# untitled8266.net
KiCad netlist of a schematic drawn in EAGLE
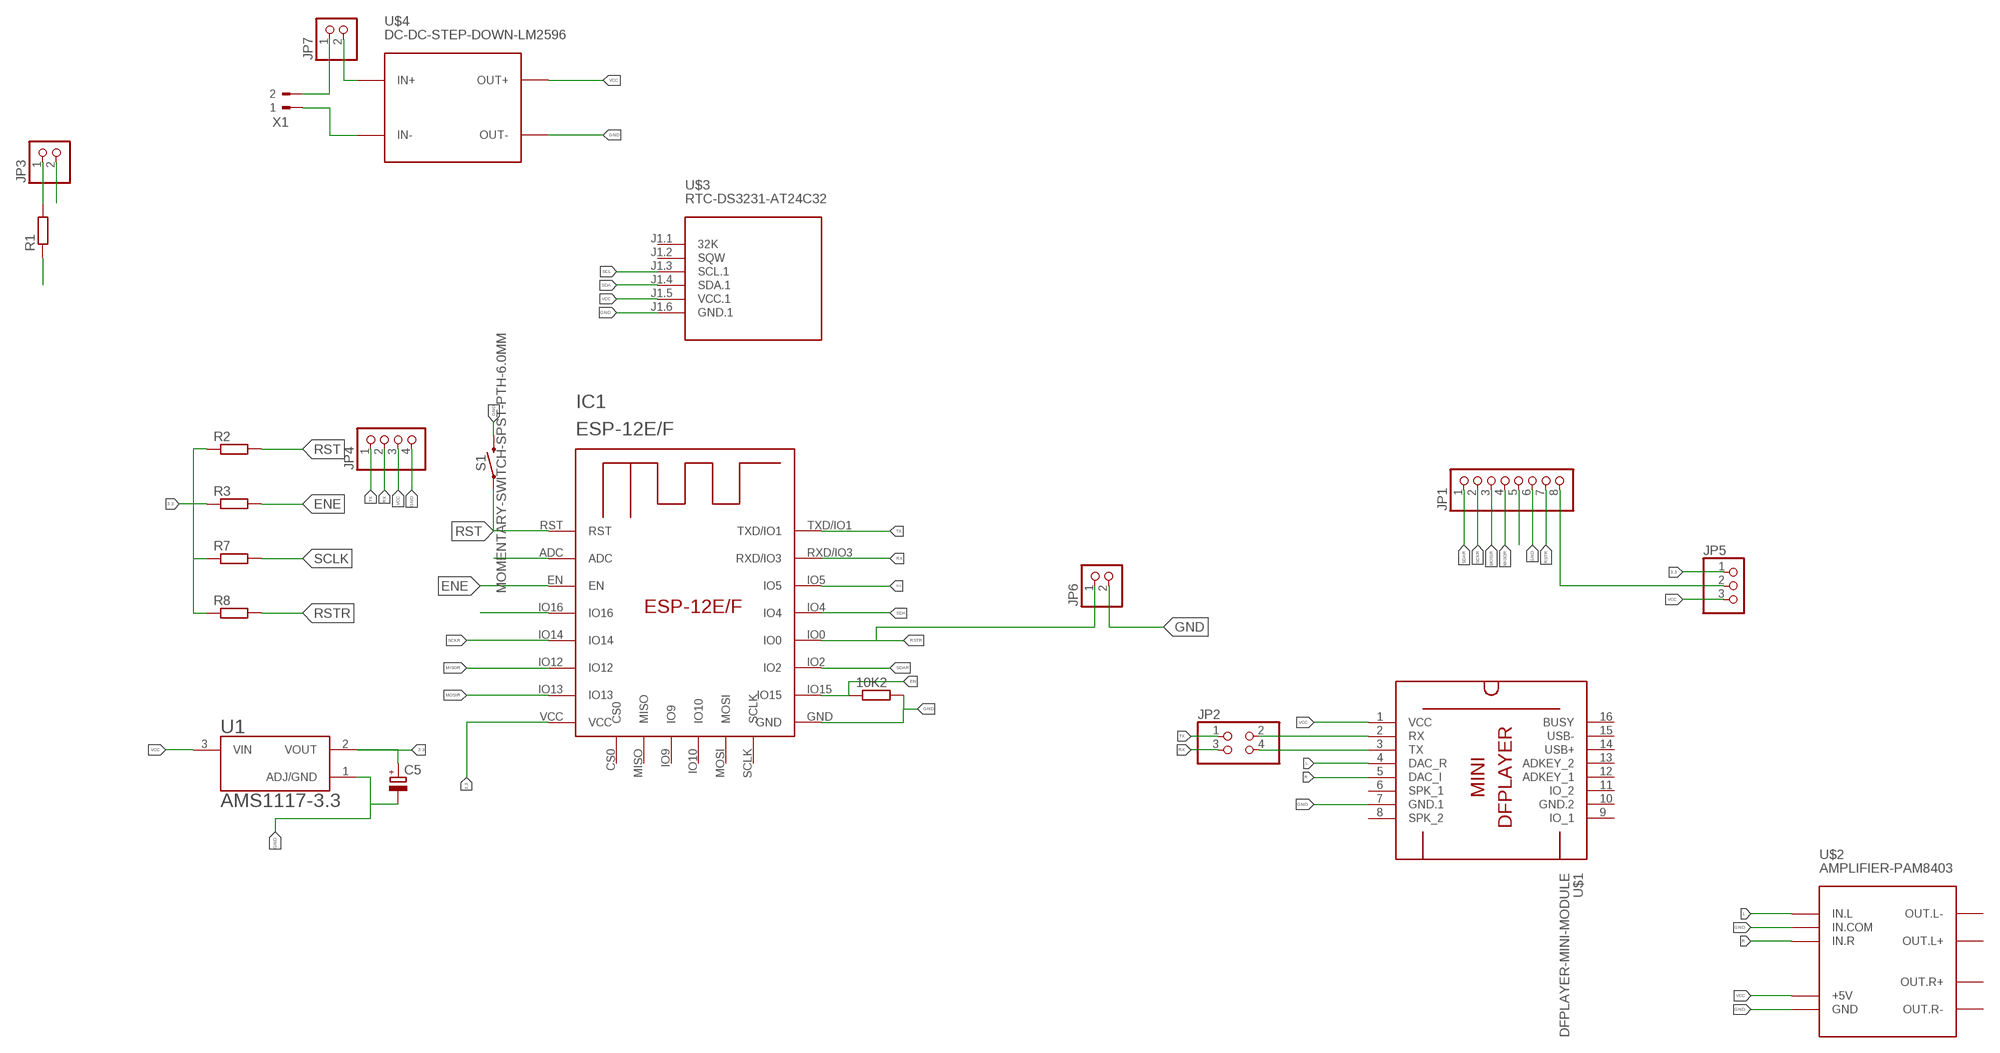
[diagram p0: schematic, sheet 1]

(export (version "E")
  (design (tool "Eeschema 10.0.6"))
  (components
    (comp (ref "10K2")
      (value "R-EU_0207/10")
      (footprint "eagle-import:0207_10")
      (libsource (lib "eagle-import") (part "R-EU_0207/10"))
    )
    (comp (ref "C5")
      (value "CPOL-EUE5-10.5")
      (footprint "eagle-import:E5-10,5")
      (libsource (lib "eagle-import") (part "CPOL-EUE5-10.5"))
    )
    (comp (ref "IC1")
      (value "ESP-12E/F")
      (footprint "eagle-import:ESP-12E")
      (libsource (lib "eagle-import") (part "ESP-12E/F"))
    )
    (comp (ref "JP1")
      (value "PINHD-1X8")
      (footprint "eagle-import:1X08")
      (libsource (lib "eagle-import") (part "PINHD-1X8"))
    )
    (comp (ref "JP2")
      (value "PINHD-2X2")
      (footprint "eagle-import:2X02")
      (libsource (lib "eagle-import") (part "PINHD-2X2"))
    )
    (comp (ref "JP3")
      (value "PINHD-1X2")
      (footprint "eagle-import:1X02")
      (libsource (lib "eagle-import") (part "PINHD-1X2"))
    )
    (comp (ref "JP4")
      (value "PINHD-1X4")
      (footprint "eagle-import:1X04")
      (libsource (lib "eagle-import") (part "PINHD-1X4"))
    )
    (comp (ref "JP5")
      (value "PINHD-1X3")
      (footprint "eagle-import:1X03")
      (libsource (lib "eagle-import") (part "PINHD-1X3"))
    )
    (comp (ref "JP6")
      (value "PINHD-1X2")
      (footprint "eagle-import:1X02")
      (libsource (lib "eagle-import") (part "PINHD-1X2"))
    )
    (comp (ref "JP7")
      (value "PINHD-1X2")
      (footprint "eagle-import:1X02")
      (libsource (lib "eagle-import") (part "PINHD-1X2"))
    )
    (comp (ref "R1")
      (value "R-EU_0207/10")
      (footprint "eagle-import:0207_10")
      (libsource (lib "eagle-import") (part "R-EU_0207/10"))
    )
    (comp (ref "R2")
      (value "R-EU_0207/10")
      (footprint "eagle-import:0207_10")
      (libsource (lib "eagle-import") (part "R-EU_0207/10"))
    )
    (comp (ref "R3")
      (value "R-EU_0207/10")
      (footprint "eagle-import:0207_10")
      (libsource (lib "eagle-import") (part "R-EU_0207/10"))
    )
    (comp (ref "R7")
      (value "R-EU_0207/10")
      (footprint "eagle-import:0207_10")
      (libsource (lib "eagle-import") (part "R-EU_0207/10"))
    )
    (comp (ref "R8")
      (value "R-EU_0207/10")
      (footprint "eagle-import:0207_10")
      (libsource (lib "eagle-import") (part "R-EU_0207/10"))
    )
    (comp (ref "S1")
      (value "MOMENTARY-SWITCH-SPST-PTH-6.0MM")
      (footprint "eagle-import:TACTILE_SWITCH_PTH_6.0MM")
      (libsource (lib "eagle-import") (part "MOMENTARY-SWITCH-SPST-PTH-6.0MM"))
    )
    (comp (ref "U$1")
      (value "DFPLAYER-MINI-MODULE")
      (footprint "eagle-import:DFPLAYER-MINI-MODULE")
      (libsource (lib "eagle-import") (part "DFPLAYER-MINI-MODULE"))
    )
    (comp (ref "U$2")
      (value "AMPLIFIER-PAM8403")
      (footprint "eagle-import:AMPLIFIER-PAM8403")
      (libsource (lib "eagle-import") (part "AMPLIFIER-PAM8403"))
    )
    (comp (ref "U$3")
      (value "RTC-DS3231-AT24C32")
      (footprint "eagle-import:RTC-DS3231-AT24C32")
      (libsource (lib "eagle-import") (part "RTC-DS3231-AT24C32"))
    )
    (comp (ref "U$4")
      (value "DC-DC-STEP-DOWN-LM2596")
      (footprint "eagle-import:DC-DC-STEP-DOWN-LM2596")
      (libsource (lib "eagle-import") (part "DC-DC-STEP-DOWN-LM2596"))
    )
    (comp (ref "U1")
      (value "AMS1117-3.3")
      (footprint "eagle-import:SOT229P700X180-4N")
      (fields (field (name "MF") "Advanced Monolithic Systems"))
      (libsource (lib "eagle-import") (part "AMS1117-3.3"))
    )
    (comp (ref "X1")
      (value "180-2")
      (footprint "eagle-import:180-2")
      (libsource (lib "eagle-import") (part "180-2"))
    )
  )
  (nets
    (net (code "1") (name "/GND.2") (class "Default")
      (node (ref "U$1") (pin "10") (pinfunction "GND.2_10") (pintype "power_in"))
    )
    (net (code "2") (name "3.3") (class "Default")
      (node (ref "C5") (pin "+") (pinfunction "+_+") (pintype "passive"))
      (node (ref "IC1") (pin "VCC") (pinfunction "VCC_VCC") (pintype "power_in"))
      (node (ref "JP5") (pin "1") (pinfunction "1_1") (pintype "passive"))
      (node (ref "R2") (pin "1") (pinfunction "1_1") (pintype "passive"))
      (node (ref "R3") (pin "1") (pinfunction "1_1") (pintype "passive"))
      (node (ref "R7") (pin "1") (pinfunction "1_1") (pintype "passive"))
      (node (ref "R8") (pin "1") (pinfunction "1_1") (pintype "passive"))
      (node (ref "U1") (pin "2") (pinfunction "VOUT_2") (pintype "output"))
    )
    (net (code "3") (name "EN") (class "Default")
      (node (ref "10K2") (pin "1") (pinfunction "1_1") (pintype "passive"))
      (node (ref "IC1") (pin "IO15") (pinfunction "IO15_IO15") (pintype "bidirectional"))
    )
    (net (code "4") (name "ENE") (class "Default")
      (node (ref "IC1") (pin "EN") (pinfunction "EN_EN") (pintype "bidirectional"))
      (node (ref "R3") (pin "2") (pinfunction "2_2") (pintype "passive"))
    )
    (net (code "5") (name "GND") (class "Default")
      (node (ref "10K2") (pin "2") (pinfunction "2_2") (pintype "passive"))
      (node (ref "C5") (pin "-") (pinfunction "-_-") (pintype "passive"))
      (node (ref "IC1") (pin "GND") (pinfunction "GND_GND") (pintype "power_in"))
      (node (ref "JP1") (pin "6") (pinfunction "6_6") (pintype "passive"))
      (node (ref "JP3") (pin "2") (pinfunction "2_2") (pintype "passive"))
      (node (ref "JP4") (pin "4") (pinfunction "4_4") (pintype "passive"))
      (node (ref "JP6") (pin "2") (pinfunction "2_2") (pintype "passive"))
      (node (ref "S1") (pin "3") (pinfunction "2_3") (pintype "passive"))
      (node (ref "U$1") (pin "7") (pinfunction "GND.1_7") (pintype "power_in"))
      (node (ref "U$2") (pin "GND") (pinfunction "GND_GND") (pintype "power_in"))
      (node (ref "U$2") (pin "IN.COM") (pinfunction "IN.COM_IN.COM") (pintype "input"))
      (node (ref "U$3") (pin "J1.6") (pinfunction "GND.1_J1.6") (pintype "power_in"))
      (node (ref "U$4") (pin "OUT-") (pinfunction "OUT-_OUT-") (pintype "bidirectional"))
      (node (ref "U1") (pin "1") (pinfunction "ADJ/GND_1") (pintype "power_in"))
    )
    (net (code "6") (name "L") (class "Default")
      (node (ref "U$1") (pin "4") (pinfunction "DAC_R_4") (pintype "bidirectional"))
      (node (ref "U$2") (pin "IN.L") (pinfunction "IN.L_IN.L") (pintype "input"))
    )
    (net (code "7") (name "MISOR") (class "Default")
      (node (ref "IC1") (pin "IO12") (pinfunction "IO12_IO12") (pintype "bidirectional"))
      (node (ref "JP1") (pin "4") (pinfunction "4_4") (pintype "passive"))
    )
    (net (code "8") (name "MOSIR") (class "Default")
      (node (ref "IC1") (pin "IO13") (pinfunction "IO13_IO13") (pintype "bidirectional"))
      (node (ref "JP1") (pin "3") (pinfunction "3_3") (pintype "passive"))
    )
    (net (code "9") (name "Net-(JP1-Pad8)") (class "Default")
      (node (ref "JP1") (pin "8") (pinfunction "8_8") (pintype "passive"))
      (node (ref "JP5") (pin "2") (pinfunction "2_2") (pintype "passive"))
    )
    (net (code "10") (name "Net-(JP3-Pad1)") (class "Default")
      (node (ref "JP3") (pin "1") (pinfunction "1_1") (pintype "passive"))
      (node (ref "R1") (pin "2") (pinfunction "2_2") (pintype "passive"))
    )
    (net (code "11") (name "Net-(JP7-Pad1)") (class "Default")
      (node (ref "JP7") (pin "1") (pinfunction "1_1") (pintype "passive"))
      (node (ref "X1") (pin "2") (pinfunction "2_2") (pintype "passive"))
    )
    (net (code "12") (name "Net-(JP7-Pad2)") (class "Default")
      (node (ref "JP7") (pin "2") (pinfunction "2_2") (pintype "passive"))
      (node (ref "U$4") (pin "IN+") (pinfunction "IN+_IN+") (pintype "bidirectional"))
    )
    (net (code "13") (name "Net-(U$1-RX)") (class "Default")
      (node (ref "JP2") (pin "2") (pinfunction "2_2") (pintype "passive"))
      (node (ref "U$1") (pin "2") (pinfunction "RX_2") (pintype "bidirectional"))
    )
    (net (code "14") (name "Net-(U$1-TX)") (class "Default")
      (node (ref "JP2") (pin "4") (pinfunction "4_4") (pintype "passive"))
      (node (ref "U$1") (pin "3") (pinfunction "TX_3") (pintype "bidirectional"))
    )
    (net (code "15") (name "Net-(U$4-PadIN-)") (class "Default")
      (node (ref "U$4") (pin "IN-") (pinfunction "IN-_IN-") (pintype "bidirectional"))
      (node (ref "X1") (pin "1") (pinfunction "1_1") (pintype "passive"))
    )
    (net (code "16") (name "R") (class "Default")
      (node (ref "U$1") (pin "5") (pinfunction "DAC_I_5") (pintype "bidirectional"))
      (node (ref "U$2") (pin "IN.R") (pinfunction "IN.R_IN.R") (pintype "bidirectional"))
    )
    (net (code "17") (name "RST") (class "Default")
      (node (ref "IC1") (pin "RST") (pinfunction "RST_RST") (pintype "input"))
      (node (ref "R2") (pin "2") (pinfunction "2_2") (pintype "passive"))
      (node (ref "S1") (pin "1") (pinfunction "1_1") (pintype "passive"))
    )
    (net (code "18") (name "RSTR") (class "Default")
      (node (ref "IC1") (pin "IO0") (pinfunction "IO0_IO0") (pintype "bidirectional"))
      (node (ref "JP1") (pin "7") (pinfunction "7_7") (pintype "passive"))
      (node (ref "JP6") (pin "1") (pinfunction "1_1") (pintype "passive"))
      (node (ref "R8") (pin "2") (pinfunction "2_2") (pintype "passive"))
    )
    (net (code "19") (name "RX") (class "Default")
      (node (ref "IC1") (pin "RXD/IO3") (pinfunction "RXD/IO3_RXD/IO3") (pintype "bidirectional"))
      (node (ref "JP2") (pin "3") (pinfunction "3_3") (pintype "passive"))
      (node (ref "JP4") (pin "2") (pinfunction "2_2") (pintype "passive"))
    )
    (net (code "20") (name "SCKR") (class "Default")
      (node (ref "IC1") (pin "IO14") (pinfunction "IO14_IO14") (pintype "bidirectional"))
      (node (ref "JP1") (pin "2") (pinfunction "2_2") (pintype "passive"))
    )
    (net (code "21") (name "SCL") (class "Default")
      (node (ref "IC1") (pin "IO5") (pinfunction "IO5_IO5") (pintype "bidirectional"))
      (node (ref "U$3") (pin "J1.3") (pinfunction "SCL.1_J1.3") (pintype "bidirectional"))
    )
    (net (code "22") (name "SCLK") (class "Default")
      (node (ref "R7") (pin "2") (pinfunction "2_2") (pintype "passive"))
    )
    (net (code "23") (name "SDA") (class "Default")
      (node (ref "IC1") (pin "IO4") (pinfunction "IO4_IO4") (pintype "bidirectional"))
      (node (ref "U$3") (pin "J1.4") (pinfunction "SDA.1_J1.4") (pintype "bidirectional"))
    )
    (net (code "24") (name "SDAR") (class "Default")
      (node (ref "IC1") (pin "IO2") (pinfunction "IO2_IO2") (pintype "bidirectional"))
      (node (ref "JP1") (pin "1") (pinfunction "1_1") (pintype "passive"))
    )
    (net (code "25") (name "TX") (class "Default")
      (node (ref "IC1") (pin "TXD/IO1") (pinfunction "TXD/IO1_TXD/IO1") (pintype "bidirectional"))
      (node (ref "JP2") (pin "1") (pinfunction "1_1") (pintype "passive"))
      (node (ref "JP4") (pin "1") (pinfunction "1_1") (pintype "passive"))
    )
    (net (code "26") (name "VCC") (class "Default")
      (node (ref "JP4") (pin "3") (pinfunction "3_3") (pintype "passive"))
      (node (ref "JP5") (pin "3") (pinfunction "3_3") (pintype "passive"))
      (node (ref "R1") (pin "1") (pinfunction "1_1") (pintype "passive"))
      (node (ref "U$1") (pin "1") (pinfunction "VCC_1") (pintype "power_in"))
      (node (ref "U$2") (pin "+5V") (pinfunction "+5V_+5V") (pintype "power_in"))
      (node (ref "U$3") (pin "J1.5") (pinfunction "VCC.1_J1.5") (pintype "power_in"))
      (node (ref "U$4") (pin "OUT+") (pinfunction "OUT+_OUT+") (pintype "bidirectional"))
      (node (ref "U1") (pin "3") (pinfunction "VIN_3") (pintype "input"))
    )
    (net (code "27") (name "unconnected-(IC1-PadADC)") (class "Default")
      (node (ref "IC1") (pin "ADC") (pinfunction "ADC_ADC") (pintype "bidirectional"))
    )
    (net (code "28") (name "unconnected-(IC1-PadCS0)") (class "Default")
      (node (ref "IC1") (pin "CS0") (pinfunction "CS0_CS0") (pintype "bidirectional"))
    )
    (net (code "29") (name "unconnected-(IC1-PadIO9)") (class "Default")
      (node (ref "IC1") (pin "IO9") (pinfunction "IO9_IO9") (pintype "bidirectional"))
    )
    (net (code "30") (name "unconnected-(IC1-PadIO10)") (class "Default")
      (node (ref "IC1") (pin "IO10") (pinfunction "IO10_IO10") (pintype "bidirectional"))
    )
    (net (code "31") (name "unconnected-(IC1-PadIO16)") (class "Default")
      (node (ref "IC1") (pin "IO16") (pinfunction "IO16_IO16") (pintype "bidirectional"))
    )
    (net (code "32") (name "unconnected-(IC1-PadMISO)") (class "Default")
      (node (ref "IC1") (pin "MISO") (pinfunction "MISO_MISO") (pintype "bidirectional"))
    )
    (net (code "33") (name "unconnected-(IC1-PadMOSI)") (class "Default")
      (node (ref "IC1") (pin "MOSI") (pinfunction "MOSI_MOSI") (pintype "bidirectional"))
    )
    (net (code "34") (name "unconnected-(IC1-PadSCLK)") (class "Default")
      (node (ref "IC1") (pin "SCLK") (pinfunction "SCLK_SCLK") (pintype "bidirectional"))
    )
    (net (code "35") (name "unconnected-(JP1-Pad5)") (class "Default")
      (node (ref "JP1") (pin "5") (pinfunction "5_5") (pintype "passive"))
    )
    (net (code "36") (name "unconnected-(U$1-ADKEY_1-Pad12)") (class "Default")
      (node (ref "U$1") (pin "12") (pinfunction "ADKEY_1_12") (pintype "bidirectional"))
    )
    (net (code "37") (name "unconnected-(U$1-ADKEY_2-Pad13)") (class "Default")
      (node (ref "U$1") (pin "13") (pinfunction "ADKEY_2_13") (pintype "bidirectional"))
    )
    (net (code "38") (name "unconnected-(U$1-BUSY-Pad16)") (class "Default")
      (node (ref "U$1") (pin "16") (pinfunction "BUSY_16") (pintype "bidirectional"))
    )
    (net (code "39") (name "unconnected-(U$1-IO_1-Pad9)") (class "Default")
      (node (ref "U$1") (pin "9") (pinfunction "IO_1_9") (pintype "bidirectional"))
    )
    (net (code "40") (name "unconnected-(U$1-IO_2-Pad11)") (class "Default")
      (node (ref "U$1") (pin "11") (pinfunction "IO_2_11") (pintype "bidirectional"))
    )
    (net (code "41") (name "unconnected-(U$1-SPK_1-Pad6)") (class "Default")
      (node (ref "U$1") (pin "6") (pinfunction "SPK_1_6") (pintype "bidirectional"))
    )
    (net (code "42") (name "unconnected-(U$1-SPK_2-Pad8)") (class "Default")
      (node (ref "U$1") (pin "8") (pinfunction "SPK_2_8") (pintype "bidirectional"))
    )
    (net (code "43") (name "unconnected-(U$1-USB+-Pad14)") (class "Default")
      (node (ref "U$1") (pin "14") (pinfunction "USB+_14") (pintype "bidirectional"))
    )
    (net (code "44") (name "unconnected-(U$1-USB--Pad15)") (class "Default")
      (node (ref "U$1") (pin "15") (pinfunction "USB-_15") (pintype "bidirectional"))
    )
    (net (code "45") (name "unconnected-(U$2-PadOUT.L+)") (class "Default")
      (node (ref "U$2") (pin "OUT.L+") (pinfunction "OUT.L+_OUT.L+") (pintype "output"))
    )
    (net (code "46") (name "unconnected-(U$2-PadOUT.L-)") (class "Default")
      (node (ref "U$2") (pin "OUT.L-") (pinfunction "OUT.L-_OUT.L-") (pintype "output"))
    )
    (net (code "47") (name "unconnected-(U$2-PadOUT.R+)") (class "Default")
      (node (ref "U$2") (pin "OUT.R+") (pinfunction "OUT.R+_OUT.R+") (pintype "output"))
    )
    (net (code "48") (name "unconnected-(U$2-PadOUT.R-)") (class "Default")
      (node (ref "U$2") (pin "OUT.R-") (pinfunction "OUT.R-_OUT.R-") (pintype "output"))
    )
    (net (code "49") (name "unconnected-(U$3-32K-PadJ1.1)") (class "Default")
      (node (ref "U$3") (pin "J1.1") (pinfunction "32K_J1.1") (pintype "bidirectional"))
    )
    (net (code "50") (name "unconnected-(U$3-SQW-PadJ1.2)") (class "Default")
      (node (ref "U$3") (pin "J1.2") (pinfunction "SQW_J1.2") (pintype "bidirectional"))
    )
  )
)
